# Placa_FdC.net
KiCad netlist of a schematic drawn in Altium Designer
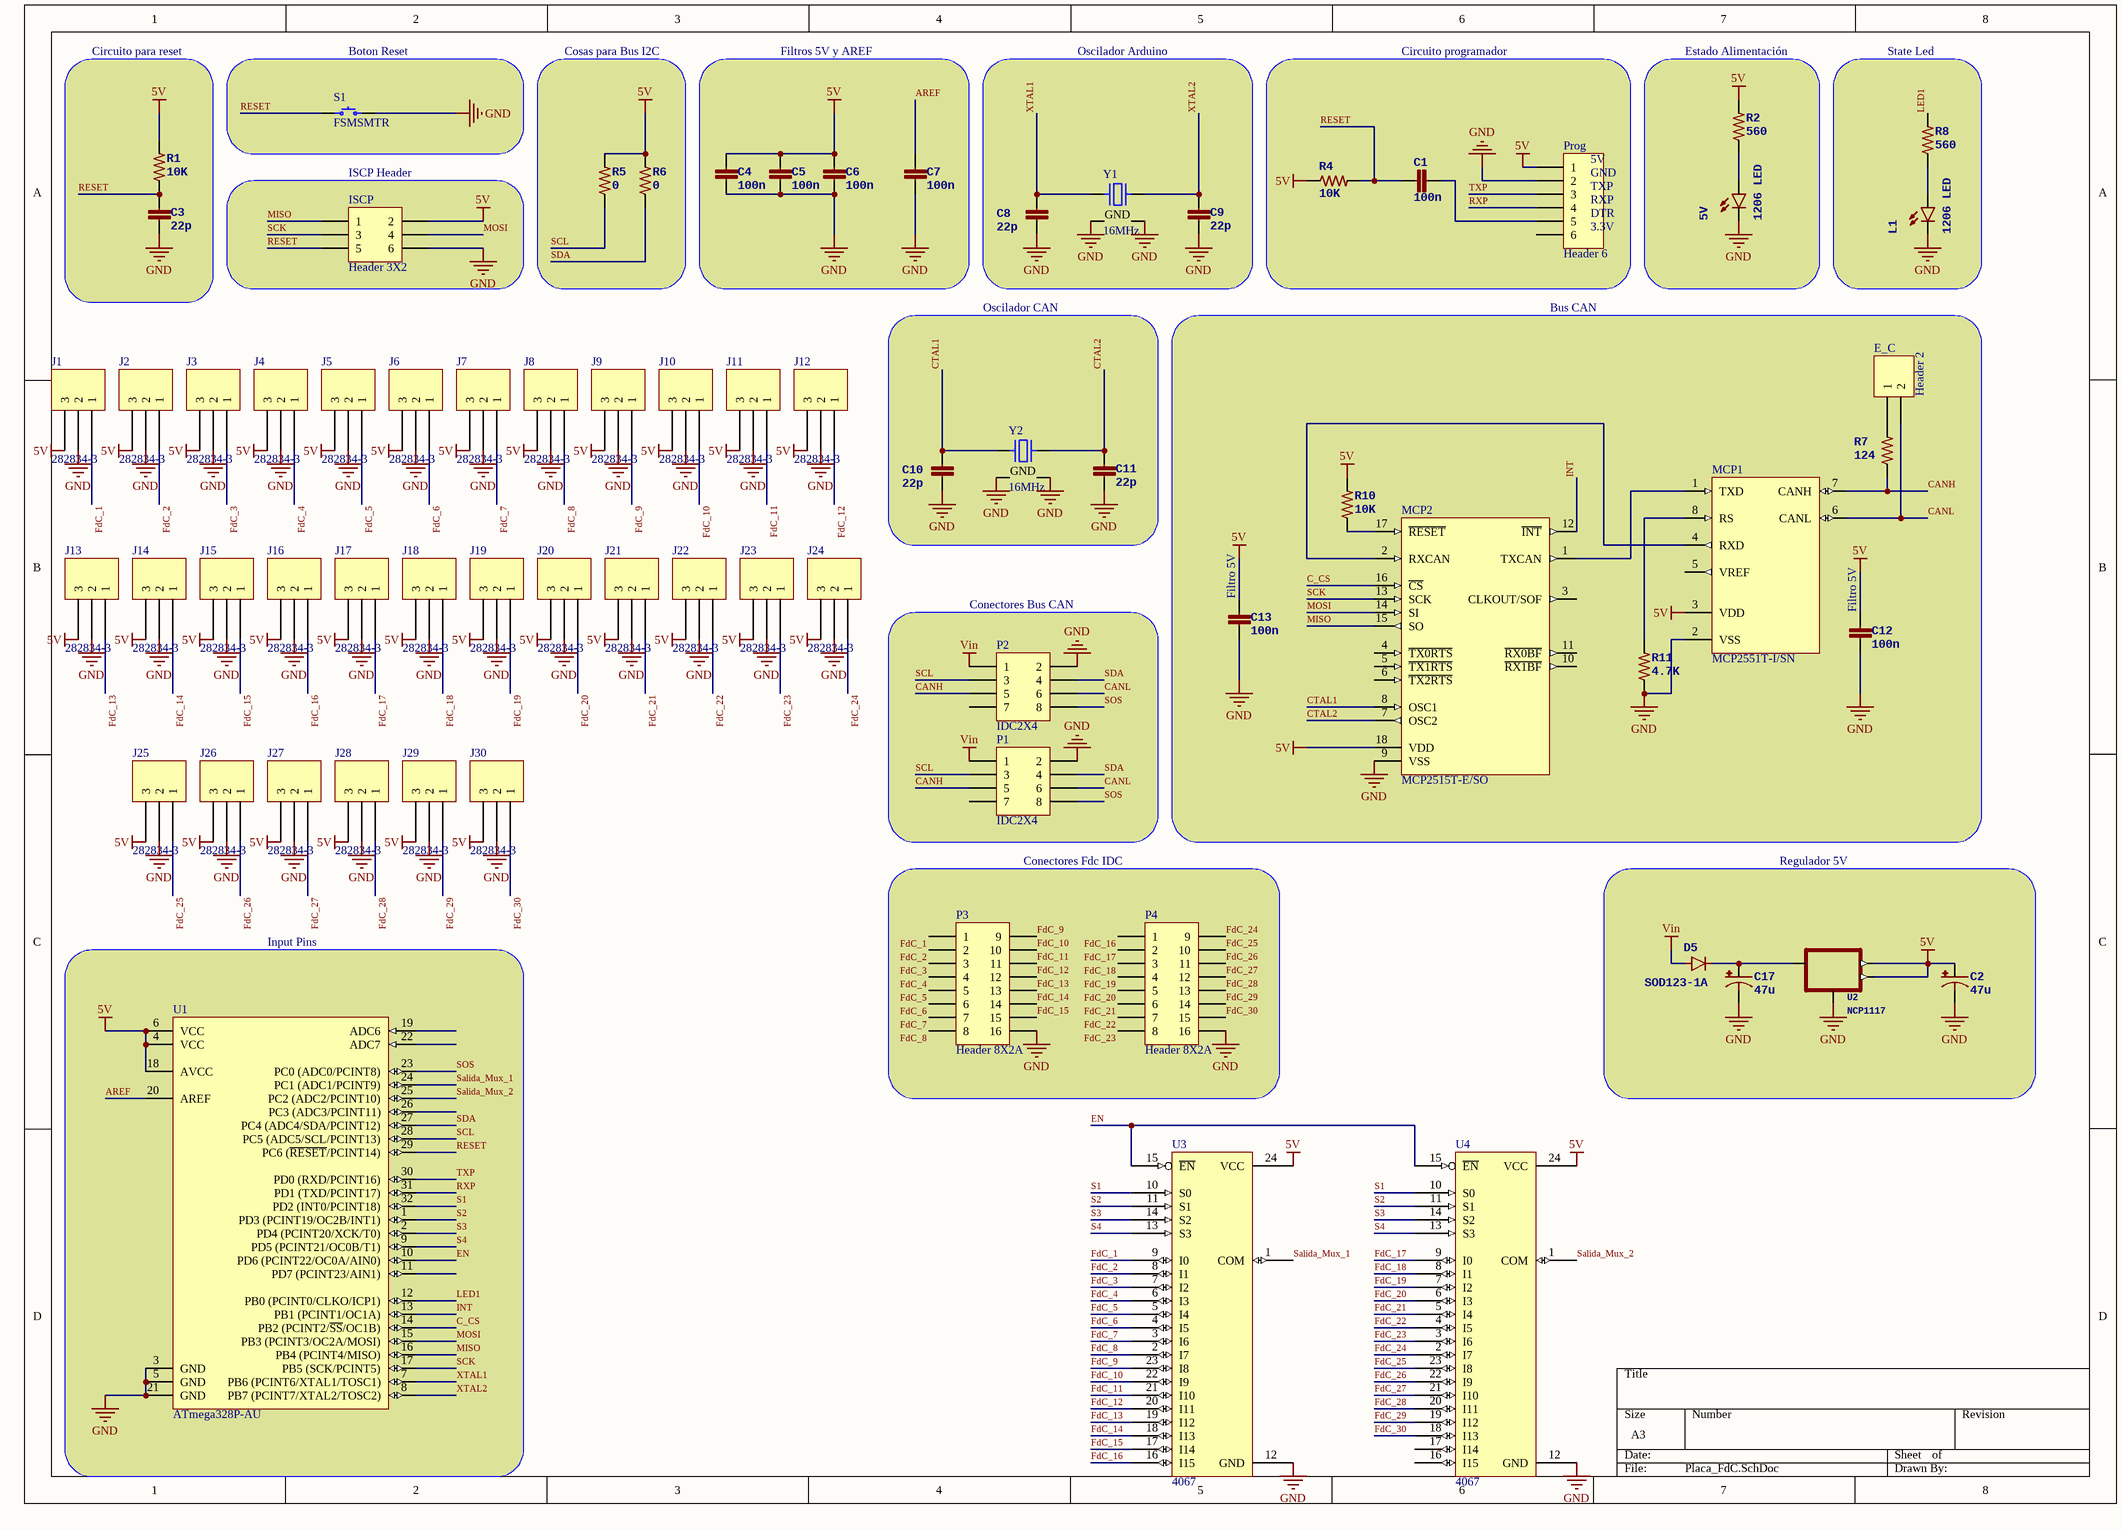
[diagram p0: Placa_FdC.SchDoc]

(export (version "E")
  (design (tool "Eeschema 10.0.6"))
  (components
    (comp (ref "5V")
      (value "1206 LED")
      (footprint "SparkFun-LED:LED-1206")
      (libsource (lib "SparkFun-LED") (part "LED1206"))
    )
    (comp (ref "C1")
      (value "100n")
      (footprint "SparkFun-Passives:0805")
      (libsource (lib "") (part "CAP0805_1"))
    )
    (comp (ref "C2")
      (value "47u")
      (footprint "PANASONIC_D")
      (libsource (lib "SparkFun-Capacitors") (part "47UF-50V-20%(ELECT)"))
    )
    (comp (ref "C3")
      (value "22p")
      (footprint "SparkFun-Passives:0805")
      (libsource (lib "SparkFun-Passives") (part "CAP0805"))
    )
    (comp (ref "C4")
      (value "100n")
      (footprint "SparkFun-Passives:0805")
      (libsource (lib "SparkFun-Passives") (part "CAP0805"))
    )
    (comp (ref "C5")
      (value "100n")
      (footprint "SparkFun-Passives:0805")
      (libsource (lib "SparkFun-Passives") (part "CAP0805"))
    )
    (comp (ref "C6")
      (value "100n")
      (footprint "SparkFun-Passives:0805")
      (libsource (lib "SparkFun-Passives") (part "CAP0805"))
    )
    (comp (ref "C7")
      (value "100n")
      (footprint "SparkFun-Passives:0805")
      (libsource (lib "SparkFun-Passives") (part "CAP0805"))
    )
    (comp (ref "C8")
      (value "22p")
      (footprint "SparkFun-Passives:0805")
      (libsource (lib "SparkFun-Passives") (part "CAP0805"))
    )
    (comp (ref "C9")
      (value "22p")
      (footprint "SparkFun-Passives:0805")
      (libsource (lib "SparkFun-Passives") (part "CAP0805"))
    )
    (comp (ref "C10")
      (value "22p")
      (footprint "SparkFun-Passives:0805")
      (libsource (lib "SparkFun-Passives") (part "CAP0805"))
    )
    (comp (ref "C11")
      (value "22p")
      (footprint "SparkFun-Passives:0805")
      (libsource (lib "SparkFun-Passives") (part "CAP0805"))
    )
    (comp (ref "C12")
      (value "100n")
      (footprint "SparkFun-Passives:0805")
      (libsource (lib "SparkFun-Passives") (part "CAP0805"))
    )
    (comp (ref "C13")
      (value "100n")
      (footprint "SparkFun-Passives:0805")
      (libsource (lib "SparkFun-Passives") (part "CAP0805"))
    )
    (comp (ref "C17")
      (value "47u")
      (footprint "PANASONIC_D")
      (libsource (lib "SparkFun-Capacitors") (part "47UF-50V-20%(ELECT)"))
    )
    (comp (ref "D5")
      (value "SOD123-1A")
      (footprint "SOD-123")
      (libsource (lib "SparkFun-DiscreteSemi") (part "DIODESOD123"))
    )
    (comp (ref "E_C")
      (value "Header 2")
      (footprint "HDR1X2")
      (description "Header, 2-Pin")
      (fields (field (name "PUBLISHER") "Altium Limited"))
      (libsource (lib "Miscellaneous Connectors") (part "Header 2"))
    )
    (comp (ref "ISCP")
      (value "Header 3X2")
      (footprint "HDR2X3")
      (description "Header, 3-Pin, Dual row")
      (fields (field (name "PUBLISHER") "Altium Limited"))
      (libsource (lib "Miscellaneous Connectors") (part "Header 3X2"))
    )
    (comp (ref "J1")
      (value "282834-3")
      (footprint "TE 282834-3")
      (description "TERM BLOCK 3POS SIDE ENT 2.54MM")
      (fields (field (name "MANUFACTURER") "TE Connectivity AMP Connectors") (field (name "VOLTAGE") "150V"))
      (libsource (lib "Celestial Library Database") (part "3 Pin"))
    )
    (comp (ref "J2")
      (value "282834-3")
      (footprint "TE 282834-3")
      (description "TERM BLOCK 3POS SIDE ENT 2.54MM")
      (fields (field (name "MANUFACTURER") "TE Connectivity AMP Connectors") (field (name "VOLTAGE") "150V"))
      (libsource (lib "Celestial Library Database") (part "3 Pin"))
    )
    (comp (ref "J3")
      (value "282834-3")
      (footprint "TE 282834-3")
      (description "TERM BLOCK 3POS SIDE ENT 2.54MM")
      (fields (field (name "MANUFACTURER") "TE Connectivity AMP Connectors") (field (name "VOLTAGE") "150V"))
      (libsource (lib "Celestial Library Database") (part "3 Pin"))
    )
    (comp (ref "J4")
      (value "282834-3")
      (footprint "TE 282834-3")
      (description "TERM BLOCK 3POS SIDE ENT 2.54MM")
      (fields (field (name "MANUFACTURER") "TE Connectivity AMP Connectors") (field (name "VOLTAGE") "150V"))
      (libsource (lib "Celestial Library Database") (part "3 Pin"))
    )
    (comp (ref "J5")
      (value "282834-3")
      (footprint "TE 282834-3")
      (description "TERM BLOCK 3POS SIDE ENT 2.54MM")
      (fields (field (name "MANUFACTURER") "TE Connectivity AMP Connectors") (field (name "VOLTAGE") "150V"))
      (libsource (lib "Celestial Library Database") (part "3 Pin"))
    )
    (comp (ref "J6")
      (value "282834-3")
      (footprint "TE 282834-3")
      (description "TERM BLOCK 3POS SIDE ENT 2.54MM")
      (fields (field (name "MANUFACTURER") "TE Connectivity AMP Connectors") (field (name "VOLTAGE") "150V"))
      (libsource (lib "Celestial Library Database") (part "3 Pin"))
    )
    (comp (ref "J7")
      (value "282834-3")
      (footprint "TE 282834-3")
      (description "TERM BLOCK 3POS SIDE ENT 2.54MM")
      (fields (field (name "MANUFACTURER") "TE Connectivity AMP Connectors") (field (name "VOLTAGE") "150V"))
      (libsource (lib "Celestial Library Database") (part "3 Pin"))
    )
    (comp (ref "J8")
      (value "282834-3")
      (footprint "TE 282834-3")
      (description "TERM BLOCK 3POS SIDE ENT 2.54MM")
      (fields (field (name "MANUFACTURER") "TE Connectivity AMP Connectors") (field (name "VOLTAGE") "150V"))
      (libsource (lib "Celestial Library Database") (part "3 Pin"))
    )
    (comp (ref "J9")
      (value "282834-3")
      (footprint "TE 282834-3")
      (description "TERM BLOCK 3POS SIDE ENT 2.54MM")
      (fields (field (name "MANUFACTURER") "TE Connectivity AMP Connectors") (field (name "VOLTAGE") "150V"))
      (libsource (lib "Celestial Library Database") (part "3 Pin"))
    )
    (comp (ref "J10")
      (value "282834-3")
      (footprint "TE 282834-3")
      (description "TERM BLOCK 3POS SIDE ENT 2.54MM")
      (fields (field (name "MANUFACTURER") "TE Connectivity AMP Connectors") (field (name "VOLTAGE") "150V"))
      (libsource (lib "Celestial Library Database") (part "3 Pin"))
    )
    (comp (ref "J11")
      (value "282834-3")
      (footprint "TE 282834-3")
      (description "TERM BLOCK 3POS SIDE ENT 2.54MM")
      (fields (field (name "MANUFACTURER") "TE Connectivity AMP Connectors") (field (name "VOLTAGE") "150V"))
      (libsource (lib "Celestial Library Database") (part "3 Pin"))
    )
    (comp (ref "J12")
      (value "282834-3")
      (footprint "TE 282834-3")
      (description "TERM BLOCK 3POS SIDE ENT 2.54MM")
      (fields (field (name "MANUFACTURER") "TE Connectivity AMP Connectors") (field (name "VOLTAGE") "150V"))
      (libsource (lib "Celestial Library Database") (part "3 Pin"))
    )
    (comp (ref "J13")
      (value "282834-3")
      (footprint "TE 282834-3")
      (description "TERM BLOCK 3POS SIDE ENT 2.54MM")
      (fields (field (name "MANUFACTURER") "TE Connectivity AMP Connectors") (field (name "VOLTAGE") "150V"))
      (libsource (lib "Celestial Library Database") (part "3 Pin"))
    )
    (comp (ref "J14")
      (value "282834-3")
      (footprint "TE 282834-3")
      (description "TERM BLOCK 3POS SIDE ENT 2.54MM")
      (fields (field (name "MANUFACTURER") "TE Connectivity AMP Connectors") (field (name "VOLTAGE") "150V"))
      (libsource (lib "Celestial Library Database") (part "3 Pin"))
    )
    (comp (ref "J15")
      (value "282834-3")
      (footprint "TE 282834-3")
      (description "TERM BLOCK 3POS SIDE ENT 2.54MM")
      (fields (field (name "MANUFACTURER") "TE Connectivity AMP Connectors") (field (name "VOLTAGE") "150V"))
      (libsource (lib "Celestial Library Database") (part "3 Pin"))
    )
    (comp (ref "J16")
      (value "282834-3")
      (footprint "TE 282834-3")
      (description "TERM BLOCK 3POS SIDE ENT 2.54MM")
      (fields (field (name "MANUFACTURER") "TE Connectivity AMP Connectors") (field (name "VOLTAGE") "150V"))
      (libsource (lib "Celestial Library Database") (part "3 Pin"))
    )
    (comp (ref "J17")
      (value "282834-3")
      (footprint "TE 282834-3")
      (description "TERM BLOCK 3POS SIDE ENT 2.54MM")
      (fields (field (name "MANUFACTURER") "TE Connectivity AMP Connectors") (field (name "VOLTAGE") "150V"))
      (libsource (lib "Celestial Library Database") (part "3 Pin"))
    )
    (comp (ref "J18")
      (value "282834-3")
      (footprint "TE 282834-3")
      (description "TERM BLOCK 3POS SIDE ENT 2.54MM")
      (fields (field (name "MANUFACTURER") "TE Connectivity AMP Connectors") (field (name "VOLTAGE") "150V"))
      (libsource (lib "Celestial Library Database") (part "3 Pin"))
    )
    (comp (ref "J19")
      (value "282834-3")
      (footprint "TE 282834-3")
      (description "TERM BLOCK 3POS SIDE ENT 2.54MM")
      (fields (field (name "MANUFACTURER") "TE Connectivity AMP Connectors") (field (name "VOLTAGE") "150V"))
      (libsource (lib "Celestial Library Database") (part "3 Pin"))
    )
    (comp (ref "J20")
      (value "282834-3")
      (footprint "TE 282834-3")
      (description "TERM BLOCK 3POS SIDE ENT 2.54MM")
      (fields (field (name "MANUFACTURER") "TE Connectivity AMP Connectors") (field (name "VOLTAGE") "150V"))
      (libsource (lib "Celestial Library Database") (part "3 Pin"))
    )
    (comp (ref "J21")
      (value "282834-3")
      (footprint "TE 282834-3")
      (description "TERM BLOCK 3POS SIDE ENT 2.54MM")
      (fields (field (name "MANUFACTURER") "TE Connectivity AMP Connectors") (field (name "VOLTAGE") "150V"))
      (libsource (lib "Celestial Library Database") (part "3 Pin"))
    )
    (comp (ref "J22")
      (value "282834-3")
      (footprint "TE 282834-3")
      (description "TERM BLOCK 3POS SIDE ENT 2.54MM")
      (fields (field (name "MANUFACTURER") "TE Connectivity AMP Connectors") (field (name "VOLTAGE") "150V"))
      (libsource (lib "Celestial Library Database") (part "3 Pin"))
    )
    (comp (ref "J23")
      (value "282834-3")
      (footprint "TE 282834-3")
      (description "TERM BLOCK 3POS SIDE ENT 2.54MM")
      (fields (field (name "MANUFACTURER") "TE Connectivity AMP Connectors") (field (name "VOLTAGE") "150V"))
      (libsource (lib "Celestial Library Database") (part "3 Pin"))
    )
    (comp (ref "J24")
      (value "282834-3")
      (footprint "TE 282834-3")
      (description "TERM BLOCK 3POS SIDE ENT 2.54MM")
      (fields (field (name "MANUFACTURER") "TE Connectivity AMP Connectors") (field (name "VOLTAGE") "150V"))
      (libsource (lib "Celestial Library Database") (part "3 Pin"))
    )
    (comp (ref "J25")
      (value "282834-3")
      (footprint "TE 282834-3")
      (description "TERM BLOCK 3POS SIDE ENT 2.54MM")
      (fields (field (name "MANUFACTURER") "TE Connectivity AMP Connectors") (field (name "VOLTAGE") "150V"))
      (libsource (lib "Celestial Library Database") (part "3 Pin"))
    )
    (comp (ref "J26")
      (value "282834-3")
      (footprint "TE 282834-3")
      (description "TERM BLOCK 3POS SIDE ENT 2.54MM")
      (fields (field (name "MANUFACTURER") "TE Connectivity AMP Connectors") (field (name "VOLTAGE") "150V"))
      (libsource (lib "Celestial Library Database") (part "3 Pin"))
    )
    (comp (ref "J27")
      (value "282834-3")
      (footprint "TE 282834-3")
      (description "TERM BLOCK 3POS SIDE ENT 2.54MM")
      (fields (field (name "MANUFACTURER") "TE Connectivity AMP Connectors") (field (name "VOLTAGE") "150V"))
      (libsource (lib "Celestial Library Database") (part "3 Pin"))
    )
    (comp (ref "J28")
      (value "282834-3")
      (footprint "TE 282834-3")
      (description "TERM BLOCK 3POS SIDE ENT 2.54MM")
      (fields (field (name "MANUFACTURER") "TE Connectivity AMP Connectors") (field (name "VOLTAGE") "150V"))
      (libsource (lib "Celestial Library Database") (part "3 Pin"))
    )
    (comp (ref "J29")
      (value "282834-3")
      (footprint "TE 282834-3")
      (description "TERM BLOCK 3POS SIDE ENT 2.54MM")
      (fields (field (name "MANUFACTURER") "TE Connectivity AMP Connectors") (field (name "VOLTAGE") "150V"))
      (libsource (lib "Celestial Library Database") (part "3 Pin"))
    )
    (comp (ref "J30")
      (value "282834-3")
      (footprint "TE 282834-3")
      (description "TERM BLOCK 3POS SIDE ENT 2.54MM")
      (fields (field (name "MANUFACTURER") "TE Connectivity AMP Connectors") (field (name "VOLTAGE") "150V"))
      (libsource (lib "Celestial Library Database") (part "3 Pin"))
    )
    (comp (ref "L1")
      (value "1206 LED")
      (footprint "SparkFun-LED:LED-1206")
      (libsource (lib "SparkFun-LED") (part "LED1206"))
    )
    (comp (ref "MCP1")
      (value "MCP2551T-I/SN")
      (footprint "SOIC-SN8_N")
      (description "High-Speed CAN Transceiver, 8-Pin SOIC, Industrial Temperature, Tape and Reel")
      (fields (field (name "PUBLISHER") "Altium Limited"))
      (libsource (lib "Microchip Interface") (part "MCP2551T-I/SN"))
    )
    (comp (ref "MCP2")
      (value "MCP2515T-E/SO")
      (footprint "SOIC-SO18_N")
      (description "Stand-Alone CAN Controller With SPI Interface, 18-Pin SOIC, Extended Temperature, Tape and Reel")
      (fields (field (name "PUBLISHER") "Altium Limited"))
      (libsource (lib "Microchip Interface") (part "MCP2515T-E/SO"))
    )
    (comp (ref "P1")
      (value "IDC2X4")
      (footprint "IDC:IDC2X4")
      (description "Header, 4-Pin, Dual row")
      (fields (field (name "PUBLISHER") "Altium Limited"))
      (libsource (lib "IDC") (part "IDC2X4"))
    )
    (comp (ref "P2")
      (value "IDC2X4")
      (footprint "IDC:IDC2X4")
      (description "Header, 4-Pin, Dual row")
      (fields (field (name "PUBLISHER") "Altium Limited"))
      (libsource (lib "IDC") (part "IDC2X4"))
    )
    (comp (ref "P3")
      (value "Header 8X2A")
      (footprint "HDR2X8_CEN")
      (description "Header, 8-Pin, Dual row")
      (fields (field (name "PUBLISHER") "Altium Limited"))
      (libsource (lib "Miscellaneous Connectors") (part "Header 8X2A"))
    )
    (comp (ref "P4")
      (value "Header 8X2A")
      (footprint "HDR2X8_CEN")
      (description "Header, 8-Pin, Dual row")
      (fields (field (name "PUBLISHER") "Altium Limited"))
      (libsource (lib "Miscellaneous Connectors") (part "Header 8X2A"))
    )
    (comp (ref "Prog")
      (value "Header 6")
      (footprint "HDR1X6")
      (description "Header, 6-Pin")
      (fields (field (name "PUBLISHER") "Altium Limited"))
      (libsource (lib "Miscellaneous Connectors") (part "Header 6"))
    )
    (comp (ref "R1")
      (value "10K")
      (footprint "SparkFun-Passives:0805")
      (libsource (lib "SparkFun-Passives") (part "RESISTOR0805-RES"))
    )
    (comp (ref "R2")
      (value "560")
      (footprint "SparkFun-Passives:0805")
      (libsource (lib "SparkFun-Passives") (part "RESISTOR0805-RES"))
    )
    (comp (ref "R4")
      (value "10K")
      (footprint "SparkFun-Passives:0805")
      (libsource (lib "SparkFun-Passives") (part "RESISTOR0805-RES"))
    )
    (comp (ref "R5")
      (value "0")
      (footprint "SparkFun-Passives:0805")
      (libsource (lib "SparkFun-Passives") (part "RESISTOR0805-RES"))
    )
    (comp (ref "R6")
      (value "0")
      (footprint "SparkFun-Passives:0805")
      (libsource (lib "SparkFun-Passives") (part "RESISTOR0805-RES"))
    )
    (comp (ref "R7")
      (value "124")
      (footprint "SparkFun-Passives:0805")
      (libsource (lib "SparkFun-Passives") (part "RESISTOR0805-RES"))
    )
    (comp (ref "R8")
      (value "560")
      (footprint "SparkFun-Passives:0805")
      (libsource (lib "SparkFun-Passives") (part "RESISTOR0805-RES"))
    )
    (comp (ref "R10")
      (value "10K")
      (footprint "SparkFun-Passives:0805")
      (libsource (lib "SparkFun-Passives") (part "RESISTOR0805-RES"))
    )
    (comp (ref "R11")
      (value "4.7K")
      (footprint "SparkFun-Passives:0805")
      (libsource (lib "SparkFun-Passives") (part "RESISTOR0805-RES"))
    )
    (comp (ref "S1")
      (value "FSMSMTR")
      (footprint "TE FSMSMTR")
      (description "SWITCH TACTILE SPST-NO 0.05A 24V")
      (fields (field (name "MANUFACTURER") "TE Connectivity Alcoswitch Switches"))
      (libsource (lib "Button - Tactile") (part "SPST-NO 2 PIN"))
    )
    (comp (ref "U1")
      (value "ATmega328P-AU")
      (footprint "32A_N")
      (fields (field (name "PUBLISHER") "Altium Limited"))
      (libsource (lib "Atmel Microcontroller 8-Bit megaAVR") (part "ATmega328P-AU"))
    )
    (comp (ref "U2")
      (value "NCP1117")
      (footprint "SparkFun-IC-Power:SOT223")
      (libsource (lib "SparkFun-IC-Power") (part "V_REG_LM1117SOT223"))
    )
    (comp (ref "U3")
      (value "4067")
      (footprint "SSOP-24")
      (description "MUX-74HC4067")
      (libsource (lib "CustomLibrary") (part "MUX-74HC4067"))
    )
    (comp (ref "U4")
      (value "4067")
      (footprint "SSOP-24")
      (description "MUX-74HC4067")
      (libsource (lib "CustomLibrary") (part "MUX-74HC4067"))
    )
    (comp (ref "Y1")
      (value "16MHz")
      (footprint "NDK NX3225SA")
      (description "CRYSTAL 16.0000MHZ 8PF SMD")
      (fields (field (name "PART NUMBER") "NX3225SA-16.000MHZ-STD-CSR-1") (field (name "MANUFACTURER") "NDK"))
      (libsource (lib "Oscillator - Crystal") (part "NDK Crystal NX3225SA"))
    )
    (comp (ref "Y2")
      (value "16MHz")
      (footprint "NDK NX3225SA")
      (description "CRYSTAL 16.0000MHZ 8PF SMD")
      (fields (field (name "PART NUMBER") "NX3225SA-16.000MHZ-STD-CSR-1") (field (name "MANUFACTURER") "NDK"))
      (libsource (lib "Oscillator - Crystal") (part "NDK Crystal NX3225SA"))
    )
  )
  (nets
    (net (code "1") (name "/AREF") (class "Default")
      (node (ref "C7") (pin "1") (pinfunction "1_1") (pintype "passive"))
      (node (ref "U1") (pin "20") (pinfunction "AREF_20") (pintype "passive"))
    )
    (net (code "2") (name "/CANH") (class "Default")
      (node (ref "MCP1") (pin "7") (pinfunction "CANH_7") (pintype "bidirectional"))
      (node (ref "P1") (pin "5") (pinfunction "5_5") (pintype "passive"))
      (node (ref "P2") (pin "5") (pinfunction "5_5") (pintype "passive"))
      (node (ref "R7") (pin "1") (pinfunction "1_1") (pintype "passive"))
    )
    (net (code "3") (name "/CANL") (class "Default")
      (node (ref "E_C") (pin "2") (pinfunction "2_2") (pintype "passive"))
      (node (ref "MCP1") (pin "6") (pinfunction "CANL_6") (pintype "bidirectional"))
      (node (ref "P1") (pin "6") (pinfunction "6_6") (pintype "passive"))
      (node (ref "P2") (pin "6") (pinfunction "6_6") (pintype "passive"))
    )
    (net (code "4") (name "/CTAL1") (class "Default")
      (node (ref "C10") (pin "1") (pinfunction "1_1") (pintype "passive"))
      (node (ref "MCP2") (pin "8") (pinfunction "OSC1_8") (pintype "input"))
      (node (ref "Y2") (pin "1") (pinfunction "1_1") (pintype "passive"))
    )
    (net (code "5") (name "/CTAL2") (class "Default")
      (node (ref "C11") (pin "1") (pinfunction "1_1") (pintype "passive"))
      (node (ref "MCP2") (pin "7") (pinfunction "OSC2_7") (pintype "output"))
      (node (ref "Y2") (pin "3") (pinfunction "3_3") (pintype "passive"))
    )
    (net (code "6") (name "/C_CS") (class "Default")
      (node (ref "MCP2") (pin "16") (pinfunction "~{CS}_16") (pintype "input"))
      (node (ref "U1") (pin "14") (pinfunction "PB2_(PCINT2/~{SS}/OC1B)_14") (pintype "bidirectional"))
    )
    (net (code "7") (name "/EN") (class "Default")
      (node (ref "U1") (pin "10") (pinfunction "PD6_(PCINT22/OC0A/AIN0)_10") (pintype "bidirectional"))
      (node (ref "U3") (pin "15") (pinfunction "~{EN}_15") (pintype "input"))
      (node (ref "U4") (pin "15") (pinfunction "~{EN}_15") (pintype "input"))
    )
    (net (code "8") (name "/FdC_1") (class "Default")
      (node (ref "J1") (pin "1") (pinfunction "1_1") (pintype "passive"))
      (node (ref "P3") (pin "1") (pinfunction "1_1") (pintype "passive"))
      (node (ref "U3") (pin "9") (pinfunction "I0_9") (pintype "bidirectional"))
    )
    (net (code "9") (name "/FdC_2") (class "Default")
      (node (ref "J2") (pin "1") (pinfunction "1_1") (pintype "passive"))
      (node (ref "P3") (pin "2") (pinfunction "2_2") (pintype "passive"))
      (node (ref "U3") (pin "8") (pinfunction "I1_8") (pintype "bidirectional"))
    )
    (net (code "10") (name "/FdC_3") (class "Default")
      (node (ref "J3") (pin "1") (pinfunction "1_1") (pintype "passive"))
      (node (ref "P3") (pin "3") (pinfunction "3_3") (pintype "passive"))
      (node (ref "U3") (pin "7") (pinfunction "I2_7") (pintype "bidirectional"))
    )
    (net (code "11") (name "/FdC_4") (class "Default")
      (node (ref "J4") (pin "1") (pinfunction "1_1") (pintype "passive"))
      (node (ref "P3") (pin "4") (pinfunction "4_4") (pintype "passive"))
      (node (ref "U3") (pin "6") (pinfunction "I3_6") (pintype "bidirectional"))
    )
    (net (code "12") (name "/FdC_5") (class "Default")
      (node (ref "J5") (pin "1") (pinfunction "1_1") (pintype "passive"))
      (node (ref "P3") (pin "5") (pinfunction "5_5") (pintype "passive"))
      (node (ref "U3") (pin "5") (pinfunction "I4_5") (pintype "bidirectional"))
    )
    (net (code "13") (name "/FdC_6") (class "Default")
      (node (ref "J6") (pin "1") (pinfunction "1_1") (pintype "passive"))
      (node (ref "P3") (pin "6") (pinfunction "6_6") (pintype "passive"))
      (node (ref "U3") (pin "4") (pinfunction "I5_4") (pintype "bidirectional"))
    )
    (net (code "14") (name "/FdC_7") (class "Default")
      (node (ref "J7") (pin "1") (pinfunction "1_1") (pintype "passive"))
      (node (ref "P3") (pin "7") (pinfunction "7_7") (pintype "passive"))
      (node (ref "U3") (pin "3") (pinfunction "I6_3") (pintype "bidirectional"))
    )
    (net (code "15") (name "/FdC_8") (class "Default")
      (node (ref "J8") (pin "1") (pinfunction "1_1") (pintype "passive"))
      (node (ref "P3") (pin "8") (pinfunction "8_8") (pintype "passive"))
      (node (ref "U3") (pin "2") (pinfunction "I7_2") (pintype "bidirectional"))
    )
    (net (code "16") (name "/FdC_9") (class "Default")
      (node (ref "J9") (pin "1") (pinfunction "1_1") (pintype "passive"))
      (node (ref "P3") (pin "9") (pinfunction "9_9") (pintype "passive"))
      (node (ref "U3") (pin "23") (pinfunction "I8_23") (pintype "bidirectional"))
    )
    (net (code "17") (name "/FdC_10") (class "Default")
      (node (ref "J10") (pin "1") (pinfunction "1_1") (pintype "passive"))
      (node (ref "P3") (pin "10") (pinfunction "10_10") (pintype "passive"))
      (node (ref "U3") (pin "22") (pinfunction "I9_22") (pintype "bidirectional"))
    )
    (net (code "18") (name "/FdC_11") (class "Default")
      (node (ref "J11") (pin "1") (pinfunction "1_1") (pintype "passive"))
      (node (ref "P3") (pin "11") (pinfunction "11_11") (pintype "passive"))
      (node (ref "U3") (pin "21") (pinfunction "I10_21") (pintype "bidirectional"))
    )
    (net (code "19") (name "/FdC_12") (class "Default")
      (node (ref "J12") (pin "1") (pinfunction "1_1") (pintype "passive"))
      (node (ref "P3") (pin "12") (pinfunction "12_12") (pintype "passive"))
      (node (ref "U3") (pin "20") (pinfunction "I11_20") (pintype "bidirectional"))
    )
    (net (code "20") (name "/FdC_13") (class "Default")
      (node (ref "J13") (pin "1") (pinfunction "1_1") (pintype "passive"))
      (node (ref "P3") (pin "13") (pinfunction "13_13") (pintype "passive"))
      (node (ref "U3") (pin "19") (pinfunction "I12_19") (pintype "bidirectional"))
    )
    (net (code "21") (name "/FdC_14") (class "Default")
      (node (ref "J14") (pin "1") (pinfunction "1_1") (pintype "passive"))
      (node (ref "P3") (pin "14") (pinfunction "14_14") (pintype "passive"))
      (node (ref "U3") (pin "18") (pinfunction "I13_18") (pintype "bidirectional"))
    )
    (net (code "22") (name "/FdC_15") (class "Default")
      (node (ref "J15") (pin "1") (pinfunction "1_1") (pintype "passive"))
      (node (ref "P3") (pin "15") (pinfunction "15_15") (pintype "passive"))
      (node (ref "U3") (pin "17") (pinfunction "I14_17") (pintype "bidirectional"))
    )
    (net (code "23") (name "/FdC_16") (class "Default")
      (node (ref "J16") (pin "1") (pinfunction "1_1") (pintype "passive"))
      (node (ref "P4") (pin "1") (pinfunction "1_1") (pintype "passive"))
      (node (ref "U3") (pin "16") (pinfunction "I15_16") (pintype "bidirectional"))
    )
    (net (code "24") (name "/FdC_17") (class "Default")
      (node (ref "J17") (pin "1") (pinfunction "1_1") (pintype "passive"))
      (node (ref "P4") (pin "2") (pinfunction "2_2") (pintype "passive"))
      (node (ref "U4") (pin "9") (pinfunction "I0_9") (pintype "bidirectional"))
    )
    (net (code "25") (name "/FdC_18") (class "Default")
      (node (ref "J18") (pin "1") (pinfunction "1_1") (pintype "passive"))
      (node (ref "P4") (pin "3") (pinfunction "3_3") (pintype "passive"))
      (node (ref "U4") (pin "8") (pinfunction "I1_8") (pintype "bidirectional"))
    )
    (net (code "26") (name "/FdC_19") (class "Default")
      (node (ref "J19") (pin "1") (pinfunction "1_1") (pintype "passive"))
      (node (ref "P4") (pin "4") (pinfunction "4_4") (pintype "passive"))
      (node (ref "U4") (pin "7") (pinfunction "I2_7") (pintype "bidirectional"))
    )
    (net (code "27") (name "/FdC_20") (class "Default")
      (node (ref "J20") (pin "1") (pinfunction "1_1") (pintype "passive"))
      (node (ref "P4") (pin "5") (pinfunction "5_5") (pintype "passive"))
      (node (ref "U4") (pin "6") (pinfunction "I3_6") (pintype "bidirectional"))
    )
    (net (code "28") (name "/FdC_21") (class "Default")
      (node (ref "J21") (pin "1") (pinfunction "1_1") (pintype "passive"))
      (node (ref "P4") (pin "6") (pinfunction "6_6") (pintype "passive"))
      (node (ref "U4") (pin "5") (pinfunction "I4_5") (pintype "bidirectional"))
    )
    (net (code "29") (name "/FdC_22") (class "Default")
      (node (ref "J22") (pin "1") (pinfunction "1_1") (pintype "passive"))
      (node (ref "P4") (pin "7") (pinfunction "7_7") (pintype "passive"))
      (node (ref "U4") (pin "4") (pinfunction "I5_4") (pintype "bidirectional"))
    )
    (net (code "30") (name "/FdC_23") (class "Default")
      (node (ref "J23") (pin "1") (pinfunction "1_1") (pintype "passive"))
      (node (ref "P4") (pin "8") (pinfunction "8_8") (pintype "passive"))
      (node (ref "U4") (pin "3") (pinfunction "I6_3") (pintype "bidirectional"))
    )
    (net (code "31") (name "/FdC_24") (class "Default")
      (node (ref "J24") (pin "1") (pinfunction "1_1") (pintype "passive"))
      (node (ref "P4") (pin "9") (pinfunction "9_9") (pintype "passive"))
      (node (ref "U4") (pin "2") (pinfunction "I7_2") (pintype "bidirectional"))
    )
    (net (code "32") (name "/FdC_25") (class "Default")
      (node (ref "J25") (pin "1") (pinfunction "1_1") (pintype "passive"))
      (node (ref "P4") (pin "10") (pinfunction "10_10") (pintype "passive"))
      (node (ref "U4") (pin "23") (pinfunction "I8_23") (pintype "bidirectional"))
    )
    (net (code "33") (name "/FdC_26") (class "Default")
      (node (ref "J26") (pin "1") (pinfunction "1_1") (pintype "passive"))
      (node (ref "P4") (pin "11") (pinfunction "11_11") (pintype "passive"))
      (node (ref "U4") (pin "22") (pinfunction "I9_22") (pintype "bidirectional"))
    )
    (net (code "34") (name "/FdC_27") (class "Default")
      (node (ref "J27") (pin "1") (pinfunction "1_1") (pintype "passive"))
      (node (ref "P4") (pin "12") (pinfunction "12_12") (pintype "passive"))
      (node (ref "U4") (pin "21") (pinfunction "I10_21") (pintype "bidirectional"))
    )
    (net (code "35") (name "/FdC_28") (class "Default")
      (node (ref "J28") (pin "1") (pinfunction "1_1") (pintype "passive"))
      (node (ref "P4") (pin "13") (pinfunction "13_13") (pintype "passive"))
      (node (ref "U4") (pin "20") (pinfunction "I11_20") (pintype "bidirectional"))
    )
    (net (code "36") (name "/FdC_29") (class "Default")
      (node (ref "J29") (pin "1") (pinfunction "1_1") (pintype "passive"))
      (node (ref "P4") (pin "14") (pinfunction "14_14") (pintype "passive"))
      (node (ref "U4") (pin "19") (pinfunction "I12_19") (pintype "bidirectional"))
    )
    (net (code "37") (name "/FdC_30") (class "Default")
      (node (ref "J30") (pin "1") (pinfunction "1_1") (pintype "passive"))
      (node (ref "P4") (pin "15") (pinfunction "15_15") (pintype "passive"))
      (node (ref "U4") (pin "18") (pinfunction "I13_18") (pintype "bidirectional"))
    )
    (net (code "38") (name "/INT") (class "Default")
      (node (ref "MCP2") (pin "12") (pinfunction "~{INT}_12") (pintype "output"))
      (node (ref "U1") (pin "13") (pinfunction "PB1_(PCINT1/OC1A)_13") (pintype "bidirectional"))
    )
    (net (code "39") (name "/LED1") (class "Default")
      (node (ref "R8") (pin "2") (pinfunction "2_2") (pintype "passive"))
      (node (ref "U1") (pin "12") (pinfunction "PB0_(PCINT0/CLKO/ICP1)_12") (pintype "bidirectional"))
    )
    (net (code "40") (name "/MISO") (class "Default")
      (node (ref "ISCP") (pin "1") (pinfunction "1_1") (pintype "passive"))
      (node (ref "MCP2") (pin "15") (pinfunction "SO_15") (pintype "output"))
      (node (ref "U1") (pin "16") (pinfunction "PB4_(PCINT4/MISO)_16") (pintype "bidirectional"))
    )
    (net (code "41") (name "/MOSI") (class "Default")
      (node (ref "ISCP") (pin "4") (pinfunction "4_4") (pintype "passive"))
      (node (ref "MCP2") (pin "14") (pinfunction "SI_14") (pintype "input"))
      (node (ref "U1") (pin "15") (pinfunction "PB3_(PCINT3/OC2A/MOSI)_15") (pintype "bidirectional"))
    )
    (net (code "42") (name "/RESET") (class "Default")
      (node (ref "C1") (pin "1") (pinfunction "1_1") (pintype "passive"))
      (node (ref "C3") (pin "1") (pinfunction "1_1") (pintype "passive"))
      (node (ref "ISCP") (pin "5") (pinfunction "5_5") (pintype "passive"))
      (node (ref "R1") (pin "1") (pinfunction "1_1") (pintype "passive"))
      (node (ref "R4") (pin "2") (pinfunction "2_2") (pintype "passive"))
      (node (ref "S1") (pin "1") (pinfunction "1_1") (pintype "passive"))
      (node (ref "U1") (pin "29") (pinfunction "PC6_(~{RESET}/PCINT14)_29") (pintype "bidirectional"))
    )
    (net (code "43") (name "/RXP") (class "Default")
      (node (ref "Prog") (pin "4") (pinfunction "4_4") (pintype "passive"))
      (node (ref "U1") (pin "31") (pinfunction "PD1_(TXD/PCINT17)_31") (pintype "bidirectional"))
    )
    (net (code "44") (name "/S1") (class "Default")
      (node (ref "U1") (pin "32") (pinfunction "PD2_(INT0/PCINT18)_32") (pintype "bidirectional"))
      (node (ref "U3") (pin "10") (pinfunction "S0_10") (pintype "input"))
      (node (ref "U4") (pin "10") (pinfunction "S0_10") (pintype "input"))
    )
    (net (code "45") (name "/S2") (class "Default")
      (node (ref "U1") (pin "1") (pinfunction "PD3_(PCINT19/OC2B/INT1)_1") (pintype "bidirectional"))
      (node (ref "U3") (pin "11") (pinfunction "S1_11") (pintype "input"))
      (node (ref "U4") (pin "11") (pinfunction "S1_11") (pintype "input"))
    )
    (net (code "46") (name "/S3") (class "Default")
      (node (ref "U1") (pin "2") (pinfunction "PD4_(PCINT20/XCK/T0)_2") (pintype "bidirectional"))
      (node (ref "U3") (pin "14") (pinfunction "S2_14") (pintype "input"))
      (node (ref "U4") (pin "14") (pinfunction "S2_14") (pintype "input"))
    )
    (net (code "47") (name "/S4") (class "Default")
      (node (ref "U1") (pin "9") (pinfunction "PD5_(PCINT21/OC0B/T1)_9") (pintype "bidirectional"))
      (node (ref "U3") (pin "13") (pinfunction "S3_13") (pintype "input"))
      (node (ref "U4") (pin "13") (pinfunction "S3_13") (pintype "input"))
    )
    (net (code "48") (name "/SCK") (class "Default")
      (node (ref "ISCP") (pin "3") (pinfunction "3_3") (pintype "passive"))
      (node (ref "MCP2") (pin "13") (pinfunction "SCK_13") (pintype "input"))
      (node (ref "U1") (pin "17") (pinfunction "PB5_(SCK/PCINT5)_17") (pintype "bidirectional"))
    )
    (net (code "49") (name "/SCL") (class "Default")
      (node (ref "P1") (pin "3") (pinfunction "3_3") (pintype "passive"))
      (node (ref "P2") (pin "3") (pinfunction "3_3") (pintype "passive"))
      (node (ref "R5") (pin "1") (pinfunction "1_1") (pintype "passive"))
      (node (ref "U1") (pin "28") (pinfunction "PC5_(ADC5/SCL/PCINT13)_28") (pintype "bidirectional"))
    )
    (net (code "50") (name "/SDA") (class "Default")
      (node (ref "P1") (pin "4") (pinfunction "4_4") (pintype "passive"))
      (node (ref "P2") (pin "4") (pinfunction "4_4") (pintype "passive"))
      (node (ref "R6") (pin "1") (pinfunction "1_1") (pintype "passive"))
      (node (ref "U1") (pin "27") (pinfunction "PC4_(ADC4/SDA/PCINT12)_27") (pintype "bidirectional"))
    )
    (net (code "51") (name "/SOS") (class "Default")
      (node (ref "P1") (pin "8") (pinfunction "8_8") (pintype "passive"))
      (node (ref "P2") (pin "8") (pinfunction "8_8") (pintype "passive"))
      (node (ref "U1") (pin "23") (pinfunction "PC0_(ADC0/PCINT8)_23") (pintype "bidirectional"))
    )
    (net (code "52") (name "/Salida_Mux_1") (class "Default")
      (node (ref "U1") (pin "24") (pinfunction "PC1_(ADC1/PCINT9)_24") (pintype "bidirectional"))
      (node (ref "U3") (pin "1") (pinfunction "COM_1") (pintype "bidirectional"))
    )
    (net (code "53") (name "/Salida_Mux_2") (class "Default")
      (node (ref "U1") (pin "25") (pinfunction "PC2_(ADC2/PCINT10)_25") (pintype "bidirectional"))
      (node (ref "U4") (pin "1") (pinfunction "COM_1") (pintype "bidirectional"))
    )
    (net (code "54") (name "/TXP") (class "Default")
      (node (ref "Prog") (pin "3") (pinfunction "3_3") (pintype "passive"))
      (node (ref "U1") (pin "30") (pinfunction "PD0_(RXD/PCINT16)_30") (pintype "bidirectional"))
    )
    (net (code "55") (name "/XTAL1") (class "Default")
      (node (ref "C8") (pin "1") (pinfunction "1_1") (pintype "passive"))
      (node (ref "U1") (pin "7") (pinfunction "PB6_(PCINT6/XTAL1/TOSC1)_7") (pintype "bidirectional"))
      (node (ref "Y1") (pin "1") (pinfunction "1_1") (pintype "passive"))
    )
    (net (code "56") (name "/XTAL2") (class "Default")
      (node (ref "C9") (pin "1") (pinfunction "1_1") (pintype "passive"))
      (node (ref "U1") (pin "8") (pinfunction "PB7_(PCINT7/XTAL2/TOSC2)_8") (pintype "bidirectional"))
      (node (ref "Y1") (pin "3") (pinfunction "3_3") (pintype "passive"))
    )
    (net (code "57") (name "5V") (class "Default")
      (node (ref "C12") (pin "1") (pinfunction "1_1") (pintype "passive"))
      (node (ref "C13") (pin "1") (pinfunction "1_1") (pintype "passive"))
      (node (ref "C2") (pin "+") (pinfunction "+_+") (pintype "passive"))
      (node (ref "C4") (pin "1") (pinfunction "1_1") (pintype "passive"))
      (node (ref "C5") (pin "1") (pinfunction "1_1") (pintype "passive"))
      (node (ref "C6") (pin "1") (pinfunction "1_1") (pintype "passive"))
      (node (ref "ISCP") (pin "2") (pinfunction "2_2") (pintype "passive"))
      (node (ref "J1") (pin "3") (pinfunction "3_3") (pintype "passive"))
      (node (ref "J10") (pin "3") (pinfunction "3_3") (pintype "passive"))
      (node (ref "J11") (pin "3") (pinfunction "3_3") (pintype "passive"))
      (node (ref "J12") (pin "3") (pinfunction "3_3") (pintype "passive"))
      (node (ref "J13") (pin "3") (pinfunction "3_3") (pintype "passive"))
      (node (ref "J14") (pin "3") (pinfunction "3_3") (pintype "passive"))
      (node (ref "J15") (pin "3") (pinfunction "3_3") (pintype "passive"))
      (node (ref "J16") (pin "3") (pinfunction "3_3") (pintype "passive"))
      (node (ref "J17") (pin "3") (pinfunction "3_3") (pintype "passive"))
      (node (ref "J18") (pin "3") (pinfunction "3_3") (pintype "passive"))
      (node (ref "J19") (pin "3") (pinfunction "3_3") (pintype "passive"))
      (node (ref "J2") (pin "3") (pinfunction "3_3") (pintype "passive"))
      (node (ref "J20") (pin "3") (pinfunction "3_3") (pintype "passive"))
      (node (ref "J21") (pin "3") (pinfunction "3_3") (pintype "passive"))
      (node (ref "J22") (pin "3") (pinfunction "3_3") (pintype "passive"))
      (node (ref "J23") (pin "3") (pinfunction "3_3") (pintype "passive"))
      (node (ref "J24") (pin "3") (pinfunction "3_3") (pintype "passive"))
      (node (ref "J25") (pin "3") (pinfunction "3_3") (pintype "passive"))
      (node (ref "J26") (pin "3") (pinfunction "3_3") (pintype "passive"))
      (node (ref "J27") (pin "3") (pinfunction "3_3") (pintype "passive"))
      (node (ref "J28") (pin "3") (pinfunction "3_3") (pintype "passive"))
      (node (ref "J29") (pin "3") (pinfunction "3_3") (pintype "passive"))
      (node (ref "J3") (pin "3") (pinfunction "3_3") (pintype "passive"))
      (node (ref "J30") (pin "3") (pinfunction "3_3") (pintype "passive"))
      (node (ref "J4") (pin "3") (pinfunction "3_3") (pintype "passive"))
      (node (ref "J5") (pin "3") (pinfunction "3_3") (pintype "passive"))
      (node (ref "J6") (pin "3") (pinfunction "3_3") (pintype "passive"))
      (node (ref "J7") (pin "3") (pinfunction "3_3") (pintype "passive"))
      (node (ref "J8") (pin "3") (pinfunction "3_3") (pintype "passive"))
      (node (ref "J9") (pin "3") (pinfunction "3_3") (pintype "passive"))
      (node (ref "MCP1") (pin "3") (pinfunction "VDD_3") (pintype "power_in"))
      (node (ref "MCP2") (pin "18") (pinfunction "VDD_18") (pintype "power_in"))
      (node (ref "Prog") (pin "1") (pinfunction "1_1") (pintype "passive"))
      (node (ref "R1") (pin "2") (pinfunction "2_2") (pintype "passive"))
      (node (ref "R10") (pin "2") (pinfunction "2_2") (pintype "passive"))
      (node (ref "R2") (pin "2") (pinfunction "2_2") (pintype "passive"))
      (node (ref "R4") (pin "1") (pinfunction "1_1") (pintype "passive"))
      (node (ref "R5") (pin "2") (pinfunction "2_2") (pintype "passive"))
      (node (ref "R6") (pin "2") (pinfunction "2_2") (pintype "passive"))
      (node (ref "U1") (pin "18") (pinfunction "AVCC_18") (pintype "power_in"))
      (node (ref "U1") (pin "4") (pinfunction "VCC_4") (pintype "power_in"))
      (node (ref "U1") (pin "6") (pinfunction "VCC_6") (pintype "power_in"))
      (node (ref "U2") (pin "2") (pinfunction "OUT_2") (pintype "output"))
      (node (ref "U2") (pin "4") (pinfunction "OUT@1_4") (pintype "output"))
      (node (ref "U3") (pin "24") (pinfunction "VCC_24") (pintype "power_in"))
      (node (ref "U4") (pin "24") (pinfunction "VCC_24") (pintype "power_in"))
    )
    (net (code "58") (name "GND") (class "Default")
      (node (ref "5V") (pin "C") (pinfunction "C_C") (pintype "passive"))
      (node (ref "C10") (pin "2") (pinfunction "2_2") (pintype "passive"))
      (node (ref "C11") (pin "2") (pinfunction "2_2") (pintype "passive"))
      (node (ref "C12") (pin "2") (pinfunction "2_2") (pintype "passive"))
      (node (ref "C13") (pin "2") (pinfunction "2_2") (pintype "passive"))
      (node (ref "C17") (pin "-") (pinfunction "-_-") (pintype "passive"))
      (node (ref "C2") (pin "-") (pinfunction "-_-") (pintype "passive"))
      (node (ref "C3") (pin "2") (pinfunction "2_2") (pintype "passive"))
      (node (ref "C4") (pin "2") (pinfunction "2_2") (pintype "passive"))
      (node (ref "C5") (pin "2") (pinfunction "2_2") (pintype "passive"))
      (node (ref "C6") (pin "2") (pinfunction "2_2") (pintype "passive"))
      (node (ref "C7") (pin "2") (pinfunction "2_2") (pintype "passive"))
      (node (ref "C8") (pin "2") (pinfunction "2_2") (pintype "passive"))
      (node (ref "C9") (pin "2") (pinfunction "2_2") (pintype "passive"))
      (node (ref "ISCP") (pin "6") (pinfunction "6_6") (pintype "passive"))
      (node (ref "J1") (pin "2") (pinfunction "2_2") (pintype "passive"))
      (node (ref "J10") (pin "2") (pinfunction "2_2") (pintype "passive"))
      (node (ref "J11") (pin "2") (pinfunction "2_2") (pintype "passive"))
      (node (ref "J12") (pin "2") (pinfunction "2_2") (pintype "passive"))
      (node (ref "J13") (pin "2") (pinfunction "2_2") (pintype "passive"))
      (node (ref "J14") (pin "2") (pinfunction "2_2") (pintype "passive"))
      (node (ref "J15") (pin "2") (pinfunction "2_2") (pintype "passive"))
      (node (ref "J16") (pin "2") (pinfunction "2_2") (pintype "passive"))
      (node (ref "J17") (pin "2") (pinfunction "2_2") (pintype "passive"))
      (node (ref "J18") (pin "2") (pinfunction "2_2") (pintype "passive"))
      (node (ref "J19") (pin "2") (pinfunction "2_2") (pintype "passive"))
      (node (ref "J2") (pin "2") (pinfunction "2_2") (pintype "passive"))
      (node (ref "J20") (pin "2") (pinfunction "2_2") (pintype "passive"))
      (node (ref "J21") (pin "2") (pinfunction "2_2") (pintype "passive"))
      (node (ref "J22") (pin "2") (pinfunction "2_2") (pintype "passive"))
      (node (ref "J23") (pin "2") (pinfunction "2_2") (pintype "passive"))
      (node (ref "J24") (pin "2") (pinfunction "2_2") (pintype "passive"))
      (node (ref "J25") (pin "2") (pinfunction "2_2") (pintype "passive"))
      (node (ref "J26") (pin "2") (pinfunction "2_2") (pintype "passive"))
      (node (ref "J27") (pin "2") (pinfunction "2_2") (pintype "passive"))
      (node (ref "J28") (pin "2") (pinfunction "2_2") (pintype "passive"))
      (node (ref "J29") (pin "2") (pinfunction "2_2") (pintype "passive"))
      (node (ref "J3") (pin "2") (pinfunction "2_2") (pintype "passive"))
      (node (ref "J30") (pin "2") (pinfunction "2_2") (pintype "passive"))
      (node (ref "J4") (pin "2") (pinfunction "2_2") (pintype "passive"))
      (node (ref "J5") (pin "2") (pinfunction "2_2") (pintype "passive"))
      (node (ref "J6") (pin "2") (pinfunction "2_2") (pintype "passive"))
      (node (ref "J7") (pin "2") (pinfunction "2_2") (pintype "passive"))
      (node (ref "J8") (pin "2") (pinfunction "2_2") (pintype "passive"))
      (node (ref "J9") (pin "2") (pinfunction "2_2") (pintype "passive"))
      (node (ref "L1") (pin "C") (pinfunction "C_C") (pintype "passive"))
      (node (ref "MCP1") (pin "2") (pinfunction "VSS_2") (pintype "power_in"))
      (node (ref "MCP2") (pin "9") (pinfunction "VSS_9") (pintype "power_in"))
      (node (ref "P1") (pin "2") (pinfunction "2_2") (pintype "passive"))
      (node (ref "P2") (pin "2") (pinfunction "2_2") (pintype "passive"))
      (node (ref "P3") (pin "16") (pinfunction "16_16") (pintype "passive"))
      (node (ref "P4") (pin "16") (pinfunction "16_16") (pintype "passive"))
      (node (ref "Prog") (pin "2") (pinfunction "2_2") (pintype "passive"))
      (node (ref "R11") (pin "1") (pinfunction "1_1") (pintype "passive"))
      (node (ref "S1") (pin "2") (pinfunction "2_2") (pintype "passive"))
      (node (ref "U1") (pin "21") (pinfunction "GND_21") (pintype "power_in"))
      (node (ref "U1") (pin "3") (pinfunction "GND_3") (pintype "power_in"))
      (node (ref "U1") (pin "5") (pinfunction "GND_5") (pintype "power_in"))
      (node (ref "U2") (pin "1") (pinfunction "ADJ_1") (pintype "passive"))
      (node (ref "U3") (pin "12") (pinfunction "GND_12") (pintype "power_in"))
      (node (ref "U4") (pin "12") (pinfunction "GND_12") (pintype "power_in"))
      (node (ref "Y1") (pin "2") (pinfunction "GND_2") (pintype "passive"))
      (node (ref "Y1") (pin "4") (pinfunction "GND_4") (pintype "passive"))
      (node (ref "Y2") (pin "2") (pinfunction "GND_2") (pintype "passive"))
      (node (ref "Y2") (pin "4") (pinfunction "GND_4") (pintype "passive"))
    )
    (net (code "59") (name "Net-(5V-PadA)") (class "Default")
      (node (ref "5V") (pin "A") (pinfunction "A_A") (pintype "passive"))
      (node (ref "R2") (pin "1") (pinfunction "1_1") (pintype "passive"))
    )
    (net (code "60") (name "Net-(C1-Pad2)") (class "Default")
      (node (ref "C1") (pin "2") (pinfunction "2_2") (pintype "passive"))
      (node (ref "Prog") (pin "5") (pinfunction "5_5") (pintype "passive"))
    )
    (net (code "61") (name "Net-(E_C-Pad1)") (class "Default")
      (node (ref "E_C") (pin "1") (pinfunction "1_1") (pintype "passive"))
      (node (ref "R7") (pin "2") (pinfunction "2_2") (pintype "passive"))
    )
    (net (code "62") (name "Net-(L1-PadA)") (class "Default")
      (node (ref "L1") (pin "A") (pinfunction "A_A") (pintype "passive"))
      (node (ref "R8") (pin "1") (pinfunction "1_1") (pintype "passive"))
    )
    (net (code "63") (name "Net-(MCP1-RS)") (class "Default")
      (node (ref "MCP1") (pin "8") (pinfunction "RS_8") (pintype "input"))
      (node (ref "R11") (pin "2") (pinfunction "2_2") (pintype "passive"))
    )
    (net (code "64") (name "Net-(MCP1-RXD)") (class "Default")
      (node (ref "MCP1") (pin "4") (pinfunction "RXD_4") (pintype "output"))
      (node (ref "MCP2") (pin "2") (pinfunction "RXCAN_2") (pintype "input"))
    )
    (net (code "65") (name "Net-(MCP1-TXD)") (class "Default")
      (node (ref "MCP1") (pin "1") (pinfunction "TXD_1") (pintype "input"))
      (node (ref "MCP2") (pin "1") (pinfunction "TXCAN_1") (pintype "output"))
    )
    (net (code "66") (name "Net-(MCP2-~{RESET})") (class "Default")
      (node (ref "MCP2") (pin "17") (pinfunction "~{RESET}_17") (pintype "input"))
      (node (ref "R10") (pin "1") (pinfunction "1_1") (pintype "passive"))
    )
    (net (code "67") (name "Net-(U2-IN)") (class "Default")
      (node (ref "C17") (pin "+") (pinfunction "+_+") (pintype "passive"))
      (node (ref "D5") (pin "C") (pinfunction "C_C") (pintype "passive"))
      (node (ref "U2") (pin "3") (pinfunction "IN_3") (pintype "passive"))
    )
    (net (code "68") (name "Vin") (class "Default")
      (node (ref "D5") (pin "A") (pinfunction "A_A") (pintype "passive"))
      (node (ref "P1") (pin "1") (pinfunction "1_1") (pintype "passive"))
      (node (ref "P2") (pin "1") (pinfunction "1_1") (pintype "passive"))
    )
    (net (code "69") (name "unconnected-(MCP1-VREF-Pad5)") (class "Default")
      (node (ref "MCP1") (pin "5") (pinfunction "VREF_5") (pintype "output"))
    )
    (net (code "70") (name "unconnected-(MCP2-CLKOUT{slash}SOF-Pad3)") (class "Default")
      (node (ref "MCP2") (pin "3") (pinfunction "CLKOUT/SOF_3") (pintype "output"))
    )
    (net (code "71") (name "unconnected-(MCP2-~{RX0BF}-Pad11)") (class "Default")
      (node (ref "MCP2") (pin "11") (pinfunction "~{RX0BF}_11") (pintype "output"))
    )
    (net (code "72") (name "unconnected-(MCP2-~{RX1BF}-Pad10)") (class "Default")
      (node (ref "MCP2") (pin "10") (pinfunction "~{RX1BF}_10") (pintype "output"))
    )
    (net (code "73") (name "unconnected-(MCP2-~{TX0RTS}-Pad4)") (class "Default")
      (node (ref "MCP2") (pin "4") (pinfunction "~{TX0RTS}_4") (pintype "input"))
    )
    (net (code "74") (name "unconnected-(MCP2-~{TX1RTS}-Pad5)") (class "Default")
      (node (ref "MCP2") (pin "5") (pinfunction "~{TX1RTS}_5") (pintype "input"))
    )
    (net (code "75") (name "unconnected-(MCP2-~{TX2RTS}-Pad6)") (class "Default")
      (node (ref "MCP2") (pin "6") (pinfunction "~{TX2RTS}_6") (pintype "input"))
    )
    (net (code "76") (name "unconnected-(P1-Pad7)") (class "Default")
      (node (ref "P1") (pin "7") (pinfunction "7_7") (pintype "passive"))
    )
    (net (code "77") (name "unconnected-(P2-Pad7)") (class "Default")
      (node (ref "P2") (pin "7") (pinfunction "7_7") (pintype "passive"))
    )
    (net (code "78") (name "unconnected-(Prog-Pad6)") (class "Default")
      (node (ref "Prog") (pin "6") (pinfunction "6_6") (pintype "passive"))
    )
    (net (code "79") (name "unconnected-(U1-ADC6-Pad19)") (class "Default")
      (node (ref "U1") (pin "19") (pinfunction "ADC6_19") (pintype "input"))
    )
    (net (code "80") (name "unconnected-(U1-ADC7-Pad22)") (class "Default")
      (node (ref "U1") (pin "22") (pinfunction "ADC7_22") (pintype "input"))
    )
    (net (code "81") (name "unconnected-(U1-PC3_(ADC3{slash}PCINT11)-Pad26)") (class "Default")
      (node (ref "U1") (pin "26") (pinfunction "PC3_(ADC3/PCINT11)_26") (pintype "bidirectional"))
    )
    (net (code "82") (name "unconnected-(U1-PD7_(PCINT23{slash}AIN1)-Pad11)") (class "Default")
      (node (ref "U1") (pin "11") (pinfunction "PD7_(PCINT23/AIN1)_11") (pintype "bidirectional"))
    )
    (net (code "83") (name "unconnected-(U4-I14-Pad17)") (class "Default")
      (node (ref "U4") (pin "17") (pinfunction "I14_17") (pintype "bidirectional"))
    )
    (net (code "84") (name "unconnected-(U4-I15-Pad16)") (class "Default")
      (node (ref "U4") (pin "16") (pinfunction "I15_16") (pintype "bidirectional"))
    )
  )
)
